# USB-ISO.net
KiCad netlist of a schematic drawn in Altium Designer
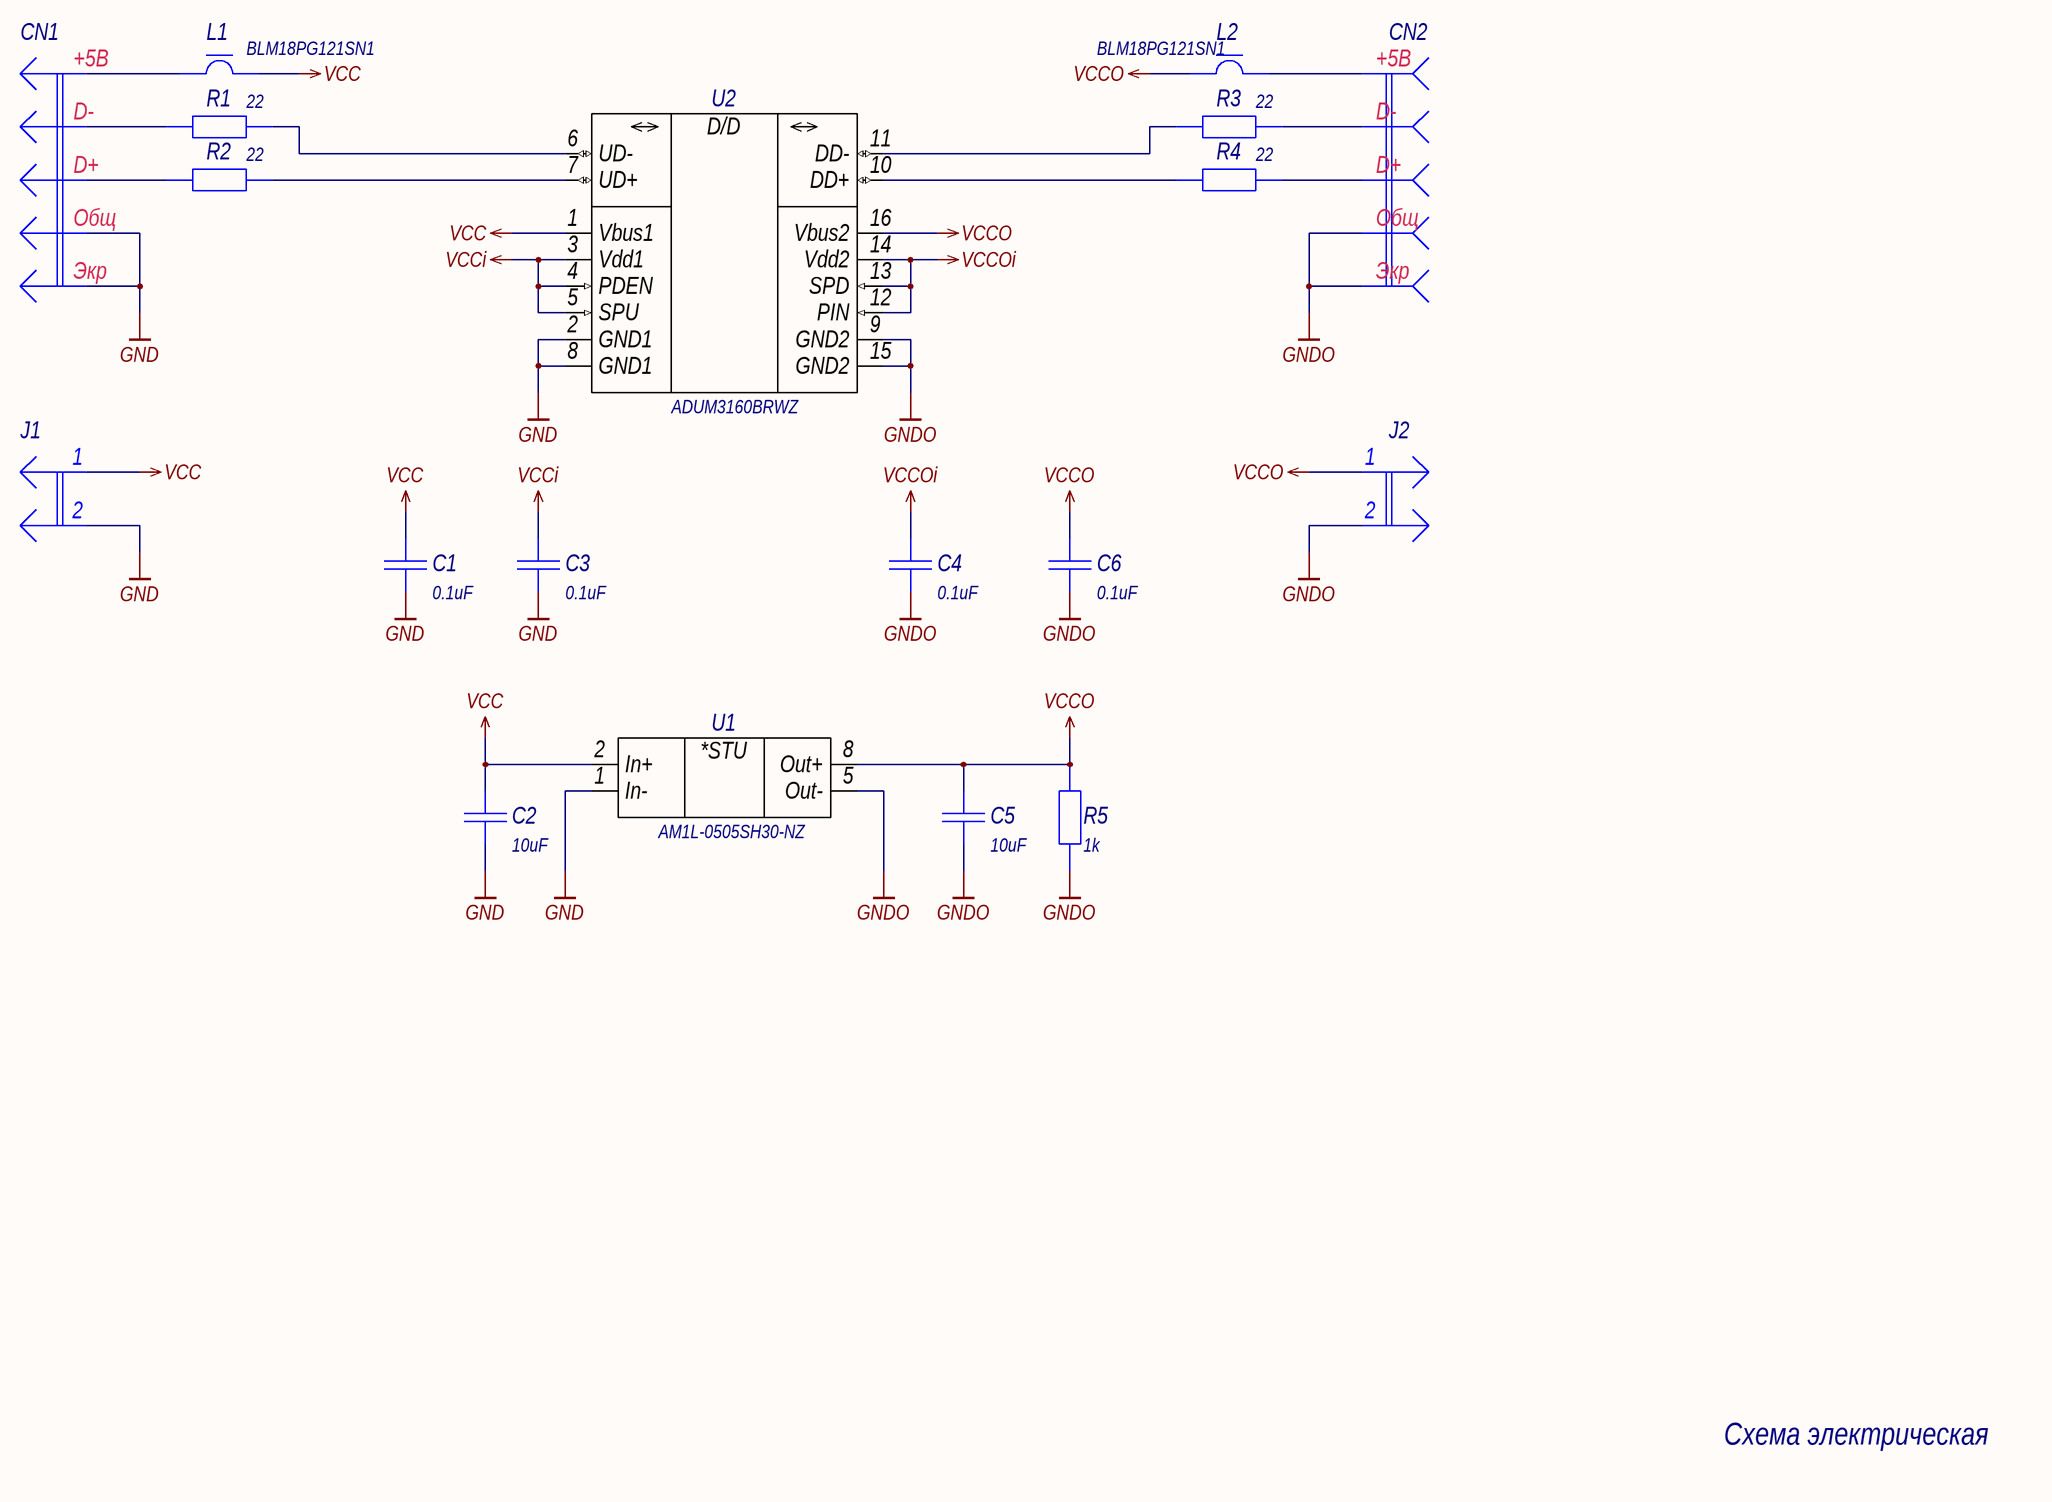
[diagram p0: USB-ISO.SchDoc]

(export (version "E")
  (design (tool "Eeschema 10.0.6"))
  (components
    (comp (ref "C1")
      (value "0.1uF")
      (footprint "C0603")
      (fields
        (field (name "PART NUMBER") "GRM188R71C104KA01D")
        (field (name "VOLTAGE") "16V")
        (field (name "TOLERANCE") "±10%")
        (field (name "PUBLISHER") "A_D")
      )
      (libsource (lib "Lib_IMP_GOST") (part "Capacitor"))
    )
    (comp (ref "C2")
      (value "10uF")
      (footprint "C0805")
      (fields
        (field (name "PART NUMBER") "GRM219R60J106KE19D")
        (field (name "VOLTAGE") "6.3V")
        (field (name "TOLERANCE") "±20%")
        (field (name "PUBLISHER") "A_D")
      )
      (libsource (lib "Lib_IMP_GOST") (part "Capacitor"))
    )
    (comp (ref "C3")
      (value "0.1uF")
      (footprint "C0603")
      (fields
        (field (name "PART NUMBER") "GRM188R71C104KA01D")
        (field (name "VOLTAGE") "16V")
        (field (name "TOLERANCE") "±10%")
        (field (name "PUBLISHER") "A_D")
      )
      (libsource (lib "Lib_IMP_GOST") (part "Capacitor"))
    )
    (comp (ref "C4")
      (value "0.1uF")
      (footprint "C0603")
      (fields
        (field (name "PART NUMBER") "GRM188R71C104KA01D")
        (field (name "VOLTAGE") "16V")
        (field (name "TOLERANCE") "±10%")
        (field (name "PUBLISHER") "A_D")
      )
      (libsource (lib "Lib_IMP_GOST") (part "Capacitor"))
    )
    (comp (ref "C5")
      (value "10uF")
      (footprint "C0805")
      (fields
        (field (name "PART NUMBER") "GRM219R60J106KE19D")
        (field (name "VOLTAGE") "6.3V")
        (field (name "TOLERANCE") "±20%")
        (field (name "PUBLISHER") "A_D")
      )
      (libsource (lib "Lib_IMP_GOST") (part "Capacitor"))
    )
    (comp (ref "C6")
      (value "0.1uF")
      (footprint "C0603")
      (fields
        (field (name "PART NUMBER") "GRM188R71C104KA01D")
        (field (name "VOLTAGE") "16V")
        (field (name "TOLERANCE") "±10%")
        (field (name "PUBLISHER") "A_D")
      )
      (libsource (lib "Lib_IMP_GOST") (part "Capacitor"))
    )
    (comp (ref "CN1")
      (value "Text")
      (footprint "DS1097")
      (fields
        (field (name "PART NUMBER") "DS1097-B")
        (field (name "MANUFACTURER") "Connfly Electronic Co., Ltd")
        (field (name "PUBLISHER") "A_D")
      )
      (libsource (lib "Lib_IMP_GOST") (part "Con-5-M-USB"))
    )
    (comp (ref "CN2")
      (value "Text")
      (footprint "DS1095")
      (fields
        (field (name "PART NUMBER") "DS1095-B-R")
        (field (name "MANUFACTURER") "Connfly Electronic Co., Ltd")
        (field (name "PUBLISHER") "A_D")
      )
      (libsource (lib "Lib_IMP_GOST") (part "Con-5-F-USB"))
    )
    (comp (ref "J1")
      (value "Text")
      (footprint "PLS-2")
      (fields (field (name "PART NUMBER") "PLS-2") (field (name "PUBLISHER") "A_D"))
      (libsource (lib "Lib_IMP_GOST") (part "Con-2-M"))
    )
    (comp (ref "J2")
      (value "Text")
      (footprint "PLS-2")
      (fields (field (name "PART NUMBER") "PLS-2") (field (name "PUBLISHER") "A_D"))
      (libsource (lib "Lib_IMP_GOST") (part "Con-2-M"))
    )
    (comp (ref "L1")
      (value "BLM18PG121SN1")
      (footprint "L0603")
      (fields
        (field (name "MANUFACTURER") "Murata")
        (field (name "Comment") "FerriteBead")
        (field (name "PUBLISHER") "A_D")
      )
      (libsource (lib "Lib_IMP_GOST") (part "FerriteBead"))
    )
    (comp (ref "L2")
      (value "BLM18PG121SN1")
      (footprint "L0603")
      (fields
        (field (name "MANUFACTURER") "Murata")
        (field (name "Comment") "FerriteBead")
        (field (name "PUBLISHER") "A_D")
      )
      (libsource (lib "Lib_IMP_GOST") (part "FerriteBead"))
    )
    (comp (ref "R1")
      (value "22")
      (footprint "R0603")
      (fields
        (field (name "PART NUMBER") "RC0603JR-0722RL")
        (field (name "TOLERANCE") "±5%")
        (field (name "MANUFACTURER") "Yageo")
        (field (name "PUBLISHER") "A_D")
      )
      (libsource (lib "Lib_IMP_GOST") (part "Resistor"))
    )
    (comp (ref "R2")
      (value "22")
      (footprint "R0603")
      (fields
        (field (name "PART NUMBER") "RC0603JR-0722RL")
        (field (name "TOLERANCE") "±5%")
        (field (name "MANUFACTURER") "Yageo")
        (field (name "PUBLISHER") "A_D")
      )
      (libsource (lib "Lib_IMP_GOST") (part "Resistor"))
    )
    (comp (ref "R3")
      (value "22")
      (footprint "R0603")
      (fields
        (field (name "PART NUMBER") "RC0603JR-0722RL")
        (field (name "TOLERANCE") "±5%")
        (field (name "MANUFACTURER") "Yageo")
        (field (name "PUBLISHER") "A_D")
      )
      (libsource (lib "Lib_IMP_GOST") (part "Resistor"))
    )
    (comp (ref "R4")
      (value "22")
      (footprint "R0603")
      (fields
        (field (name "PART NUMBER") "RC0603JR-0722RL")
        (field (name "TOLERANCE") "±5%")
        (field (name "MANUFACTURER") "Yageo")
        (field (name "PUBLISHER") "A_D")
      )
      (libsource (lib "Lib_IMP_GOST") (part "Resistor"))
    )
    (comp (ref "R5")
      (value "1k")
      (footprint "R0603")
      (fields
        (field (name "PART NUMBER") "RC0603JR-071KL")
        (field (name "TOLERANCE") "±5%")
        (field (name "MANUFACTURER") "Yageo")
        (field (name "PUBLISHER") "A_D")
      )
      (libsource (lib "Lib_IMP_GOST") (part "Resistor"))
    )
    (comp (ref "U1")
      (value "AM1L-0505SH30-NZ")
      (footprint "AM1L-xxxxDH30-NZ-Series")
      (fields
        (field (name "MANUFACTURER") "Aimtec")
        (field (name "Comment") "AM1L-xxxxSH30-Series")
        (field (name "PUBLISHER") "A_D")
      )
      (libsource (lib "Lib_IMP_GOST") (part "AM1L-xxxxSH30-Series"))
    )
    (comp (ref "U2")
      (value "ADUM3160BRWZ")
      (footprint "SOIC-16W")
      (fields
        (field (name "MANUFACTURER") "Analog Devices")
        (field (name "Comment") "ADuMx160-Series")
        (field (name "PUBLISHER") "A_D")
      )
      (libsource (lib "Lib_IMP_GOST") (part "ADuMx160-Series"))
    )
  )
  (nets
    (net (code "1") (name "GND") (class "Default")
      (node (ref "C1") (pin "1") (pinfunction "1_1") (pintype "passive"))
      (node (ref "C2") (pin "1") (pinfunction "1_1") (pintype "passive"))
      (node (ref "C3") (pin "1") (pinfunction "1_1") (pintype "passive"))
      (node (ref "CN1") (pin "4") (pintype "passive"))
      (node (ref "CN1") (pin "5") (pintype "passive"))
      (node (ref "J1") (pin "2") (pintype "passive"))
      (node (ref "U1") (pin "1") (pinfunction "In-_1") (pintype "power_in"))
      (node (ref "U2") (pin "2") (pinfunction "GND1_2") (pintype "power_in"))
      (node (ref "U2") (pin "8") (pinfunction "GND1_8") (pintype "power_in"))
    )
    (net (code "2") (name "GNDO") (class "Default")
      (node (ref "C4") (pin "1") (pinfunction "1_1") (pintype "passive"))
      (node (ref "C5") (pin "1") (pinfunction "1_1") (pintype "passive"))
      (node (ref "C6") (pin "1") (pinfunction "1_1") (pintype "passive"))
      (node (ref "CN2") (pin "4") (pintype "passive"))
      (node (ref "CN2") (pin "5") (pintype "passive"))
      (node (ref "J2") (pin "2") (pintype "passive"))
      (node (ref "R5") (pin "1") (pinfunction "1_1") (pintype "passive"))
      (node (ref "U1") (pin "5") (pinfunction "Out-_5") (pintype "power_in"))
      (node (ref "U2") (pin "15") (pinfunction "GND2_15") (pintype "power_in"))
      (node (ref "U2") (pin "9") (pinfunction "GND2_9") (pintype "power_in"))
    )
    (net (code "3") (name "Net-(CN1-Pad1)") (class "Default")
      (node (ref "CN1") (pin "1") (pintype "passive"))
      (node (ref "L1") (pin "1") (pinfunction "1_1") (pintype "passive"))
    )
    (net (code "4") (name "Net-(CN1-Pad2)") (class "Default")
      (node (ref "CN1") (pin "2") (pintype "passive"))
      (node (ref "R1") (pin "1") (pinfunction "1_1") (pintype "passive"))
    )
    (net (code "5") (name "Net-(CN1-Pad3)") (class "Default")
      (node (ref "CN1") (pin "3") (pintype "passive"))
      (node (ref "R2") (pin "1") (pinfunction "1_1") (pintype "passive"))
    )
    (net (code "6") (name "Net-(CN2-Pad1)") (class "Default")
      (node (ref "CN2") (pin "1") (pintype "passive"))
      (node (ref "L2") (pin "2") (pinfunction "2_2") (pintype "passive"))
    )
    (net (code "7") (name "Net-(CN2-Pad2)") (class "Default")
      (node (ref "CN2") (pin "2") (pintype "passive"))
      (node (ref "R3") (pin "1") (pinfunction "1_1") (pintype "passive"))
    )
    (net (code "8") (name "Net-(CN2-Pad3)") (class "Default")
      (node (ref "CN2") (pin "3") (pintype "passive"))
      (node (ref "R4") (pin "1") (pinfunction "1_1") (pintype "passive"))
    )
    (net (code "9") (name "Net-(U2-DD+)") (class "Default")
      (node (ref "R4") (pin "2") (pinfunction "2_2") (pintype "passive"))
      (node (ref "U2") (pin "10") (pinfunction "DD+_10") (pintype "bidirectional"))
    )
    (net (code "10") (name "Net-(U2-DD-)") (class "Default")
      (node (ref "R3") (pin "2") (pinfunction "2_2") (pintype "passive"))
      (node (ref "U2") (pin "11") (pinfunction "DD-_11") (pintype "bidirectional"))
    )
    (net (code "11") (name "Net-(U2-UD+)") (class "Default")
      (node (ref "R2") (pin "2") (pinfunction "2_2") (pintype "passive"))
      (node (ref "U2") (pin "7") (pinfunction "UD+_7") (pintype "bidirectional"))
    )
    (net (code "12") (name "Net-(U2-UD-)") (class "Default")
      (node (ref "R1") (pin "2") (pinfunction "2_2") (pintype "passive"))
      (node (ref "U2") (pin "6") (pinfunction "UD-_6") (pintype "bidirectional"))
    )
    (net (code "13") (name "VCC") (class "Default")
      (node (ref "C1") (pin "2") (pinfunction "2_2") (pintype "passive"))
      (node (ref "C2") (pin "2") (pinfunction "2_2") (pintype "passive"))
      (node (ref "J1") (pin "1") (pintype "passive"))
      (node (ref "L1") (pin "2") (pinfunction "2_2") (pintype "passive"))
      (node (ref "U1") (pin "2") (pinfunction "In+_2") (pintype "power_in"))
      (node (ref "U2") (pin "1") (pinfunction "Vbus1_1") (pintype "power_in"))
    )
    (net (code "14") (name "VCCO") (class "Default")
      (node (ref "C5") (pin "2") (pinfunction "2_2") (pintype "passive"))
      (node (ref "C6") (pin "2") (pinfunction "2_2") (pintype "passive"))
      (node (ref "J2") (pin "1") (pintype "passive"))
      (node (ref "L2") (pin "1") (pinfunction "1_1") (pintype "passive"))
      (node (ref "R5") (pin "2") (pinfunction "2_2") (pintype "passive"))
      (node (ref "U1") (pin "8") (pinfunction "Out+_8") (pintype "power_in"))
      (node (ref "U2") (pin "16") (pinfunction "Vbus2_16") (pintype "power_in"))
    )
    (net (code "15") (name "VCCOi") (class "Default")
      (node (ref "C4") (pin "2") (pinfunction "2_2") (pintype "passive"))
      (node (ref "U2") (pin "12") (pinfunction "PIN_12") (pintype "input"))
      (node (ref "U2") (pin "13") (pinfunction "SPD_13") (pintype "input"))
      (node (ref "U2") (pin "14") (pinfunction "Vdd2_14") (pintype "power_in"))
    )
    (net (code "16") (name "VCCi") (class "Default")
      (node (ref "C3") (pin "2") (pinfunction "2_2") (pintype "passive"))
      (node (ref "U2") (pin "3") (pinfunction "Vdd1_3") (pintype "power_in"))
      (node (ref "U2") (pin "4") (pinfunction "PDEN_4") (pintype "input"))
      (node (ref "U2") (pin "5") (pinfunction "SPU_5") (pintype "input"))
    )
  )
)
